# BUZZERR.net
KiCad netlist of a schematic drawn in EAGLE
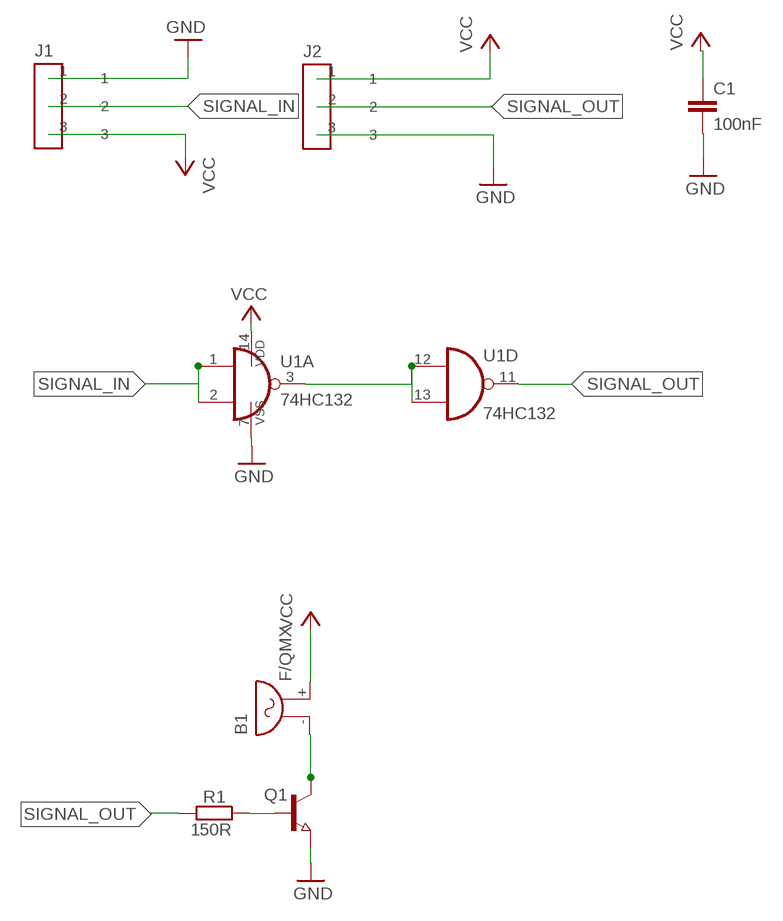
[diagram p0: schematic, sheet 1]

(export (version "E")
  (design (tool "Eeschema 10.0.6"))
  (components
    (comp (ref "B1")
      (value "F/QMX")
      (footprint "eagle-import:F_QMX")
      (libsource (lib "eagle-import") (part "F/QMX"))
    )
    (comp (ref "C1")
      (value "100nF")
      (footprint "eagle-import:C0805")
      (libsource (lib "eagle-import") (part "C-EUC0805"))
    )
    (comp (ref "J1")
      (value "CONECTOR_MACHO")
      (footprint "eagle-import:3CONECTOR")
      (libsource (lib "eagle-import") (part "CONECTOR_MACHO"))
    )
    (comp (ref "J2")
      (value "CONECTOR_FEMEA")
      (footprint "eagle-import:3CONECTOR")
      (libsource (lib "eagle-import") (part "CONECTOR_FEMEA"))
    )
    (comp (ref "Q1")
      (value "BC817")
      (footprint "eagle-import:SOT23")
      (libsource (lib "eagle-import") (part "NPN-TRANSISTOR_SOT23"))
    )
    (comp (ref "R1")
      (value "150R")
      (footprint "eagle-import:R0805W")
      (libsource (lib "eagle-import") (part "R-EU_R0805W"))
    )
    (comp (ref "U1")
      (value "74HC132")
      (footprint "eagle-import:SO14")
      (libsource (lib "eagle-import") (part "4011D"))
    )
  )
  (nets
    (net (code "1") (name "GND") (class "Default")
      (node (ref "C1") (pin "2") (pinfunction "2_2") (pintype "passive"))
      (node (ref "J1") (pin "1") (pinfunction "1_1") (pintype "bidirectional"))
      (node (ref "J2") (pin "3") (pinfunction "3_3") (pintype "bidirectional"))
      (node (ref "Q1") (pin "2") (pinfunction "E_2") (pintype "passive"))
      (node (ref "U1") (pin "7") (pinfunction "VSS_7") (pintype "power_in"))
    )
    (net (code "2") (name "Net-(B1-1)") (class "Default")
      (node (ref "B1") (pin "-") (pinfunction "1_-") (pintype "passive"))
      (node (ref "Q1") (pin "3") (pinfunction "C_3") (pintype "passive"))
    )
    (net (code "3") (name "Net-(Q1-B)") (class "Default")
      (node (ref "Q1") (pin "1") (pinfunction "B_1") (pintype "passive"))
      (node (ref "R1") (pin "1") (pinfunction "1_1") (pintype "passive"))
    )
    (net (code "4") (name "Net-(U1A-O)") (class "Default")
      (node (ref "U1") (pin "12") (pinfunction "I0_12") (pintype "input"))
      (node (ref "U1") (pin "13") (pinfunction "I1_13") (pintype "input"))
      (node (ref "U1") (pin "3") (pinfunction "O_3") (pintype "output"))
    )
    (net (code "5") (name "SIGNAL_IN") (class "Default")
      (node (ref "J1") (pin "2") (pinfunction "2_2") (pintype "bidirectional"))
      (node (ref "U1") (pin "1") (pinfunction "I0_1") (pintype "input"))
      (node (ref "U1") (pin "2") (pinfunction "I1_2") (pintype "input"))
    )
    (net (code "6") (name "SIGNAL_OUT") (class "Default")
      (node (ref "J2") (pin "2") (pinfunction "2_2") (pintype "bidirectional"))
      (node (ref "R1") (pin "2") (pinfunction "2_2") (pintype "passive"))
      (node (ref "U1") (pin "11") (pinfunction "O_11") (pintype "output"))
    )
    (net (code "7") (name "VCC") (class "Default")
      (node (ref "B1") (pin "+") (pinfunction "2_+") (pintype "passive"))
      (node (ref "C1") (pin "1") (pinfunction "1_1") (pintype "passive"))
      (node (ref "J1") (pin "3") (pinfunction "3_3") (pintype "bidirectional"))
      (node (ref "J2") (pin "1") (pinfunction "1_1") (pintype "bidirectional"))
      (node (ref "U1") (pin "14") (pinfunction "VDD_14") (pintype "power_in"))
    )
  )
)
